# PlusCartUnified3.net
KiCad netlist of a schematic drawn in EAGLE
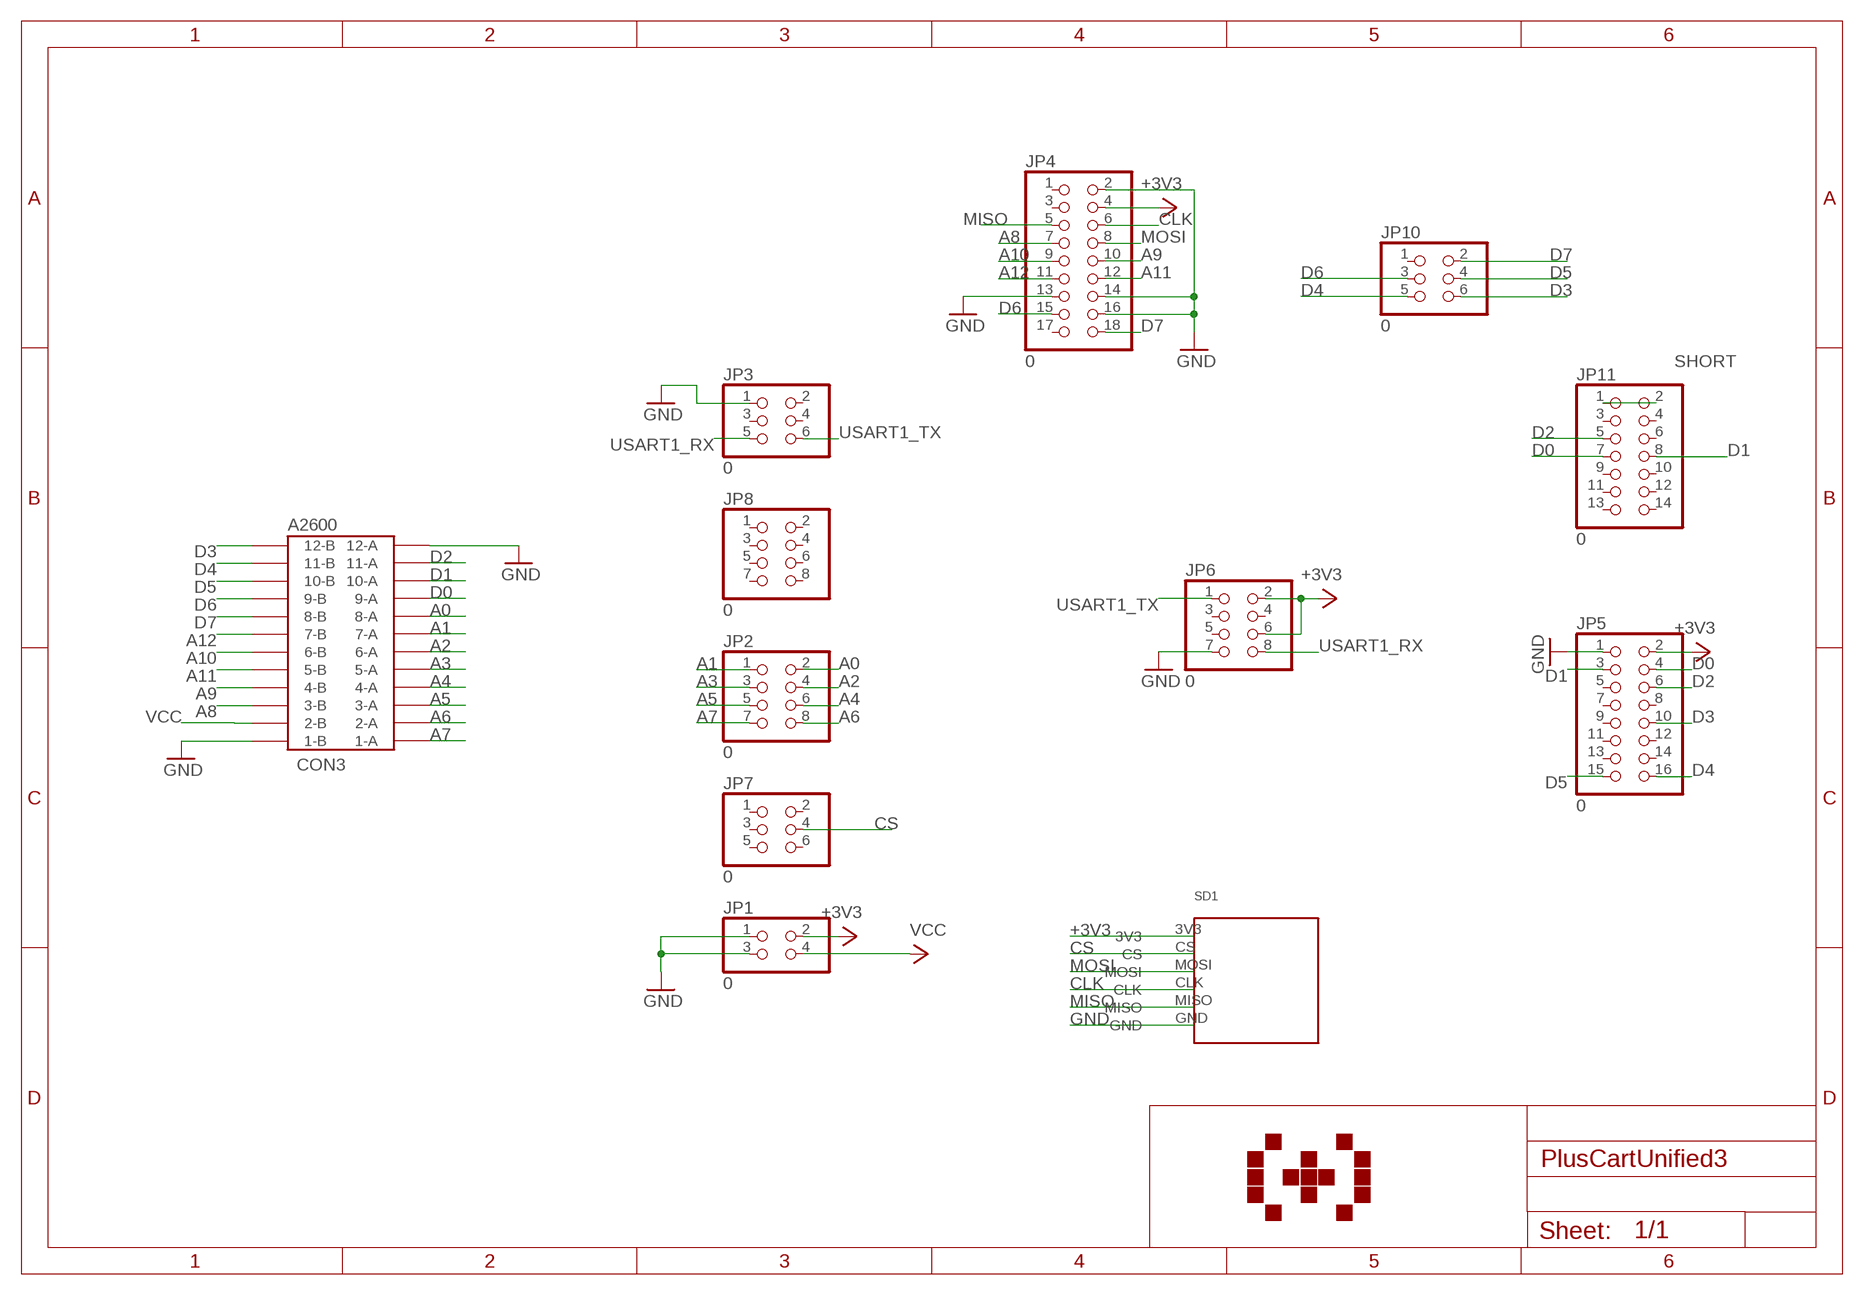
[diagram p0: schematic, sheet 1]

(export (version "E")
  (design (tool "Eeschema 10.0.6"))
  (components
    (comp (ref "CON3")
      (value "A2600")
      (footprint "eagle-import:24PINEDGE-254MM")
      (libsource (lib "eagle-import") (part "24PINEDGE-254MM"))
    )
    (comp (ref "JP1")
      (value "0")
      (footprint "eagle-import:2X02")
      (libsource (lib "eagle-import") (part "PINHD-2X2"))
    )
    (comp (ref "JP2")
      (value "0")
      (footprint "eagle-import:2X04")
      (libsource (lib "eagle-import") (part "PINHD-2X4"))
    )
    (comp (ref "JP3")
      (value "0")
      (footprint "eagle-import:2X03")
      (libsource (lib "eagle-import") (part "PINHD-2X3"))
    )
    (comp (ref "JP4")
      (value "0")
      (footprint "eagle-import:2X09")
      (libsource (lib "eagle-import") (part "PINHD-2X9"))
    )
    (comp (ref "JP5")
      (value "0")
      (footprint "eagle-import:2X08")
      (libsource (lib "eagle-import") (part "PINHD-2X8"))
    )
    (comp (ref "JP6")
      (value "0")
      (footprint "eagle-import:2X04")
      (libsource (lib "eagle-import") (part "PINHD-2X4"))
    )
    (comp (ref "JP7")
      (value "0")
      (footprint "eagle-import:2X03")
      (libsource (lib "eagle-import") (part "pinhead@1_PINHD-2X3"))
    )
    (comp (ref "JP8")
      (value "0")
      (footprint "eagle-import:2X04")
      (libsource (lib "eagle-import") (part "pinhead@1_PINHD-2X4"))
    )
    (comp (ref "JP10")
      (value "0")
      (footprint "eagle-import:2X03")
      (libsource (lib "eagle-import") (part "pinhead@1_PINHD-2X3"))
    )
    (comp (ref "JP11")
      (value "0")
      (footprint "eagle-import:2X07")
      (libsource (lib "eagle-import") (part "PINHD-2X7"))
    )
    (comp (ref "SD1")
      (value "MICROSDMICROSD2")
      (footprint "eagle-import:MICROSD_FOOTPRINT")
      (libsource (lib "eagle-import") (part "MICROSDMICROSD2"))
    )
  )
  (nets
    (net (code "1") (name "+3V3") (class "Default")
      (node (ref "JP1") (pin "2") (pinfunction "2_2") (pintype "passive"))
      (node (ref "JP4") (pin "4") (pinfunction "4_4") (pintype "passive"))
      (node (ref "JP5") (pin "2") (pinfunction "2_2") (pintype "passive"))
      (node (ref "JP6") (pin "2") (pinfunction "2_2") (pintype "passive"))
      (node (ref "JP6") (pin "6") (pinfunction "6_6") (pintype "passive"))
      (node (ref "SD1") (pin "3V3") (pinfunction "3V3_3V3") (pintype "bidirectional"))
    )
    (net (code "2") (name "/A0") (class "Default")
      (node (ref "CON3") (pin "8-A") (pinfunction "8-A_8-A") (pintype "passive"))
      (node (ref "JP2") (pin "2") (pinfunction "2_2") (pintype "passive"))
    )
    (net (code "3") (name "/A1") (class "Default")
      (node (ref "CON3") (pin "7-A") (pinfunction "7-A_7-A") (pintype "passive"))
      (node (ref "JP2") (pin "1") (pinfunction "1_1") (pintype "passive"))
    )
    (net (code "4") (name "/A2") (class "Default")
      (node (ref "CON3") (pin "6-A") (pinfunction "6-A_6-A") (pintype "passive"))
      (node (ref "JP2") (pin "4") (pinfunction "4_4") (pintype "passive"))
    )
    (net (code "5") (name "/A3") (class "Default")
      (node (ref "CON3") (pin "5-A") (pinfunction "5-A_5-A") (pintype "passive"))
      (node (ref "JP2") (pin "3") (pinfunction "3_3") (pintype "passive"))
    )
    (net (code "6") (name "/A4") (class "Default")
      (node (ref "CON3") (pin "4-A") (pinfunction "4-A_4-A") (pintype "passive"))
      (node (ref "JP2") (pin "6") (pinfunction "6_6") (pintype "passive"))
    )
    (net (code "7") (name "/A5") (class "Default")
      (node (ref "CON3") (pin "3-A") (pinfunction "3-A_3-A") (pintype "passive"))
      (node (ref "JP2") (pin "5") (pinfunction "5_5") (pintype "passive"))
    )
    (net (code "8") (name "/A6") (class "Default")
      (node (ref "CON3") (pin "2-A") (pinfunction "2-A_2-A") (pintype "passive"))
      (node (ref "JP2") (pin "8") (pinfunction "8_8") (pintype "passive"))
    )
    (net (code "9") (name "/A7") (class "Default")
      (node (ref "CON3") (pin "1-A") (pinfunction "1-A_1-A") (pintype "passive"))
      (node (ref "JP2") (pin "7") (pinfunction "7_7") (pintype "passive"))
    )
    (net (code "10") (name "/A8") (class "Default")
      (node (ref "CON3") (pin "3-B") (pinfunction "3-B_3-B") (pintype "passive"))
      (node (ref "JP4") (pin "7") (pinfunction "7_7") (pintype "passive"))
    )
    (net (code "11") (name "/A9") (class "Default")
      (node (ref "CON3") (pin "4-B") (pinfunction "4-B_4-B") (pintype "passive"))
      (node (ref "JP4") (pin "10") (pinfunction "10_10") (pintype "passive"))
    )
    (net (code "12") (name "/A10") (class "Default")
      (node (ref "CON3") (pin "6-B") (pinfunction "6-B_6-B") (pintype "passive"))
      (node (ref "JP4") (pin "9") (pinfunction "9_9") (pintype "passive"))
    )
    (net (code "13") (name "/A11") (class "Default")
      (node (ref "CON3") (pin "5-B") (pinfunction "5-B_5-B") (pintype "passive"))
      (node (ref "JP4") (pin "12") (pinfunction "12_12") (pintype "passive"))
    )
    (net (code "14") (name "/A12") (class "Default")
      (node (ref "CON3") (pin "7-B") (pinfunction "7-B_7-B") (pintype "passive"))
      (node (ref "JP4") (pin "11") (pinfunction "11_11") (pintype "passive"))
    )
    (net (code "15") (name "/CLK") (class "Default")
      (node (ref "JP4") (pin "6") (pinfunction "6_6") (pintype "passive"))
      (node (ref "SD1") (pin "CLK") (pinfunction "CLK_CLK") (pintype "bidirectional"))
    )
    (net (code "16") (name "/CS") (class "Default")
      (node (ref "JP7") (pin "4") (pinfunction "4_4") (pintype "passive"))
      (node (ref "SD1") (pin "CS") (pinfunction "CS_CS") (pintype "bidirectional"))
    )
    (net (code "17") (name "/D0") (class "Default")
      (node (ref "CON3") (pin "9-A") (pinfunction "9-A_9-A") (pintype "passive"))
      (node (ref "JP11") (pin "7") (pinfunction "7_7") (pintype "passive"))
      (node (ref "JP5") (pin "4") (pinfunction "4_4") (pintype "passive"))
    )
    (net (code "18") (name "/D1") (class "Default")
      (node (ref "CON3") (pin "10-A") (pinfunction "10-A_10-A") (pintype "passive"))
      (node (ref "JP11") (pin "8") (pinfunction "8_8") (pintype "passive"))
      (node (ref "JP5") (pin "3") (pinfunction "3_3") (pintype "passive"))
    )
    (net (code "19") (name "/D2") (class "Default")
      (node (ref "CON3") (pin "11-A") (pinfunction "11-A_11-A") (pintype "passive"))
      (node (ref "JP11") (pin "5") (pinfunction "5_5") (pintype "passive"))
      (node (ref "JP5") (pin "6") (pinfunction "6_6") (pintype "passive"))
    )
    (net (code "20") (name "/D3") (class "Default")
      (node (ref "CON3") (pin "12-B") (pinfunction "12-B_12-B") (pintype "passive"))
      (node (ref "JP10") (pin "6") (pinfunction "6_6") (pintype "passive"))
      (node (ref "JP5") (pin "10") (pinfunction "10_10") (pintype "passive"))
    )
    (net (code "21") (name "/D4") (class "Default")
      (node (ref "CON3") (pin "11-B") (pinfunction "11-B_11-B") (pintype "passive"))
      (node (ref "JP10") (pin "5") (pinfunction "5_5") (pintype "passive"))
      (node (ref "JP5") (pin "16") (pinfunction "16_16") (pintype "passive"))
    )
    (net (code "22") (name "/D5") (class "Default")
      (node (ref "CON3") (pin "10-B") (pinfunction "10-B_10-B") (pintype "passive"))
      (node (ref "JP10") (pin "4") (pinfunction "4_4") (pintype "passive"))
      (node (ref "JP5") (pin "15") (pinfunction "15_15") (pintype "passive"))
    )
    (net (code "23") (name "/D6") (class "Default")
      (node (ref "CON3") (pin "9-B") (pinfunction "9-B_9-B") (pintype "passive"))
      (node (ref "JP10") (pin "3") (pinfunction "3_3") (pintype "passive"))
      (node (ref "JP4") (pin "15") (pinfunction "15_15") (pintype "passive"))
    )
    (net (code "24") (name "/D7") (class "Default")
      (node (ref "CON3") (pin "8-B") (pinfunction "8-B_8-B") (pintype "passive"))
      (node (ref "JP10") (pin "2") (pinfunction "2_2") (pintype "passive"))
      (node (ref "JP4") (pin "18") (pinfunction "18_18") (pintype "passive"))
    )
    (net (code "25") (name "/MISO") (class "Default")
      (node (ref "JP4") (pin "5") (pinfunction "5_5") (pintype "passive"))
      (node (ref "SD1") (pin "MISO") (pinfunction "MISO_MISO") (pintype "bidirectional"))
    )
    (net (code "26") (name "/MOSI") (class "Default")
      (node (ref "JP4") (pin "8") (pinfunction "8_8") (pintype "passive"))
      (node (ref "SD1") (pin "MOSI") (pinfunction "MOSI_MOSI") (pintype "bidirectional"))
    )
    (net (code "27") (name "/SHORT") (class "Default")
      (node (ref "JP11") (pin "1") (pinfunction "1_1") (pintype "passive"))
      (node (ref "JP11") (pin "2") (pinfunction "2_2") (pintype "passive"))
    )
    (net (code "28") (name "/USART1_RX") (class "Default")
      (node (ref "JP3") (pin "5") (pinfunction "5_5") (pintype "passive"))
      (node (ref "JP6") (pin "8") (pinfunction "8_8") (pintype "passive"))
    )
    (net (code "29") (name "/USART1_TX") (class "Default")
      (node (ref "JP3") (pin "6") (pinfunction "6_6") (pintype "passive"))
      (node (ref "JP6") (pin "1") (pinfunction "1_1") (pintype "passive"))
    )
    (net (code "30") (name "GND") (class "Default")
      (node (ref "CON3") (pin "1-B") (pinfunction "1-B_1-B") (pintype "passive"))
      (node (ref "CON3") (pin "12-A") (pinfunction "12-A_12-A") (pintype "passive"))
      (node (ref "JP1") (pin "1") (pinfunction "1_1") (pintype "passive"))
      (node (ref "JP1") (pin "3") (pinfunction "3_3") (pintype "passive"))
      (node (ref "JP3") (pin "1") (pinfunction "1_1") (pintype "passive"))
      (node (ref "JP4") (pin "13") (pinfunction "13_13") (pintype "passive"))
      (node (ref "JP4") (pin "14") (pinfunction "14_14") (pintype "passive"))
      (node (ref "JP4") (pin "16") (pinfunction "16_16") (pintype "passive"))
      (node (ref "JP4") (pin "2") (pinfunction "2_2") (pintype "passive"))
      (node (ref "JP5") (pin "1") (pinfunction "1_1") (pintype "passive"))
      (node (ref "JP6") (pin "7") (pinfunction "7_7") (pintype "passive"))
      (node (ref "SD1") (pin "GND") (pinfunction "GND_GND") (pintype "bidirectional"))
    )
    (net (code "31") (name "VCC") (class "Default")
      (node (ref "CON3") (pin "2-B") (pinfunction "2-B_2-B") (pintype "passive"))
      (node (ref "JP1") (pin "4") (pinfunction "4_4") (pintype "passive"))
    )
    (net (code "32") (name "unconnected-(JP3-Pad2)") (class "Default")
      (node (ref "JP3") (pin "2") (pinfunction "2_2") (pintype "passive"))
    )
    (net (code "33") (name "unconnected-(JP3-Pad3)") (class "Default")
      (node (ref "JP3") (pin "3") (pinfunction "3_3") (pintype "passive"))
    )
    (net (code "34") (name "unconnected-(JP3-Pad4)") (class "Default")
      (node (ref "JP3") (pin "4") (pinfunction "4_4") (pintype "passive"))
    )
    (net (code "35") (name "unconnected-(JP4-Pad1)") (class "Default")
      (node (ref "JP4") (pin "1") (pinfunction "1_1") (pintype "passive"))
    )
    (net (code "36") (name "unconnected-(JP4-Pad3)") (class "Default")
      (node (ref "JP4") (pin "3") (pinfunction "3_3") (pintype "passive"))
    )
    (net (code "37") (name "unconnected-(JP4-Pad17)") (class "Default")
      (node (ref "JP4") (pin "17") (pinfunction "17_17") (pintype "passive"))
    )
    (net (code "38") (name "unconnected-(JP5-Pad5)") (class "Default")
      (node (ref "JP5") (pin "5") (pinfunction "5_5") (pintype "passive"))
    )
    (net (code "39") (name "unconnected-(JP5-Pad7)") (class "Default")
      (node (ref "JP5") (pin "7") (pinfunction "7_7") (pintype "passive"))
    )
    (net (code "40") (name "unconnected-(JP5-Pad8)") (class "Default")
      (node (ref "JP5") (pin "8") (pinfunction "8_8") (pintype "passive"))
    )
    (net (code "41") (name "unconnected-(JP5-Pad9)") (class "Default")
      (node (ref "JP5") (pin "9") (pinfunction "9_9") (pintype "passive"))
    )
    (net (code "42") (name "unconnected-(JP5-Pad11)") (class "Default")
      (node (ref "JP5") (pin "11") (pinfunction "11_11") (pintype "passive"))
    )
    (net (code "43") (name "unconnected-(JP5-Pad12)") (class "Default")
      (node (ref "JP5") (pin "12") (pinfunction "12_12") (pintype "passive"))
    )
    (net (code "44") (name "unconnected-(JP5-Pad13)") (class "Default")
      (node (ref "JP5") (pin "13") (pinfunction "13_13") (pintype "passive"))
    )
    (net (code "45") (name "unconnected-(JP5-Pad14)") (class "Default")
      (node (ref "JP5") (pin "14") (pinfunction "14_14") (pintype "passive"))
    )
    (net (code "46") (name "unconnected-(JP6-Pad3)") (class "Default")
      (node (ref "JP6") (pin "3") (pinfunction "3_3") (pintype "passive"))
    )
    (net (code "47") (name "unconnected-(JP6-Pad4)") (class "Default")
      (node (ref "JP6") (pin "4") (pinfunction "4_4") (pintype "passive"))
    )
    (net (code "48") (name "unconnected-(JP6-Pad5)") (class "Default")
      (node (ref "JP6") (pin "5") (pinfunction "5_5") (pintype "passive"))
    )
    (net (code "49") (name "unconnected-(JP7-Pad1)") (class "Default")
      (node (ref "JP7") (pin "1") (pinfunction "1_1") (pintype "passive"))
    )
    (net (code "50") (name "unconnected-(JP7-Pad2)") (class "Default")
      (node (ref "JP7") (pin "2") (pinfunction "2_2") (pintype "passive"))
    )
    (net (code "51") (name "unconnected-(JP7-Pad3)") (class "Default")
      (node (ref "JP7") (pin "3") (pinfunction "3_3") (pintype "passive"))
    )
    (net (code "52") (name "unconnected-(JP7-Pad5)") (class "Default")
      (node (ref "JP7") (pin "5") (pinfunction "5_5") (pintype "passive"))
    )
    (net (code "53") (name "unconnected-(JP7-Pad6)") (class "Default")
      (node (ref "JP7") (pin "6") (pinfunction "6_6") (pintype "passive"))
    )
    (net (code "54") (name "unconnected-(JP8-Pad1)") (class "Default")
      (node (ref "JP8") (pin "1") (pinfunction "1_1") (pintype "passive"))
    )
    (net (code "55") (name "unconnected-(JP8-Pad2)") (class "Default")
      (node (ref "JP8") (pin "2") (pinfunction "2_2") (pintype "passive"))
    )
    (net (code "56") (name "unconnected-(JP8-Pad3)") (class "Default")
      (node (ref "JP8") (pin "3") (pinfunction "3_3") (pintype "passive"))
    )
    (net (code "57") (name "unconnected-(JP8-Pad4)") (class "Default")
      (node (ref "JP8") (pin "4") (pinfunction "4_4") (pintype "passive"))
    )
    (net (code "58") (name "unconnected-(JP8-Pad5)") (class "Default")
      (node (ref "JP8") (pin "5") (pinfunction "5_5") (pintype "passive"))
    )
    (net (code "59") (name "unconnected-(JP8-Pad6)") (class "Default")
      (node (ref "JP8") (pin "6") (pinfunction "6_6") (pintype "passive"))
    )
    (net (code "60") (name "unconnected-(JP8-Pad7)") (class "Default")
      (node (ref "JP8") (pin "7") (pinfunction "7_7") (pintype "passive"))
    )
    (net (code "61") (name "unconnected-(JP8-Pad8)") (class "Default")
      (node (ref "JP8") (pin "8") (pinfunction "8_8") (pintype "passive"))
    )
    (net (code "62") (name "unconnected-(JP10-Pad1)") (class "Default")
      (node (ref "JP10") (pin "1") (pinfunction "1_1") (pintype "passive"))
    )
    (net (code "63") (name "unconnected-(JP11-Pad3)") (class "Default")
      (node (ref "JP11") (pin "3") (pinfunction "3_3") (pintype "passive"))
    )
    (net (code "64") (name "unconnected-(JP11-Pad4)") (class "Default")
      (node (ref "JP11") (pin "4") (pinfunction "4_4") (pintype "passive"))
    )
    (net (code "65") (name "unconnected-(JP11-Pad6)") (class "Default")
      (node (ref "JP11") (pin "6") (pinfunction "6_6") (pintype "passive"))
    )
    (net (code "66") (name "unconnected-(JP11-Pad9)") (class "Default")
      (node (ref "JP11") (pin "9") (pinfunction "9_9") (pintype "passive"))
    )
    (net (code "67") (name "unconnected-(JP11-Pad10)") (class "Default")
      (node (ref "JP11") (pin "10") (pinfunction "10_10") (pintype "passive"))
    )
    (net (code "68") (name "unconnected-(JP11-Pad11)") (class "Default")
      (node (ref "JP11") (pin "11") (pinfunction "11_11") (pintype "passive"))
    )
    (net (code "69") (name "unconnected-(JP11-Pad12)") (class "Default")
      (node (ref "JP11") (pin "12") (pinfunction "12_12") (pintype "passive"))
    )
    (net (code "70") (name "unconnected-(JP11-Pad13)") (class "Default")
      (node (ref "JP11") (pin "13") (pinfunction "13_13") (pintype "passive"))
    )
    (net (code "71") (name "unconnected-(JP11-Pad14)") (class "Default")
      (node (ref "JP11") (pin "14") (pinfunction "14_14") (pintype "passive"))
    )
  )
)
